# FitFullBoard.net
KiCad netlist of a schematic drawn in EAGLE
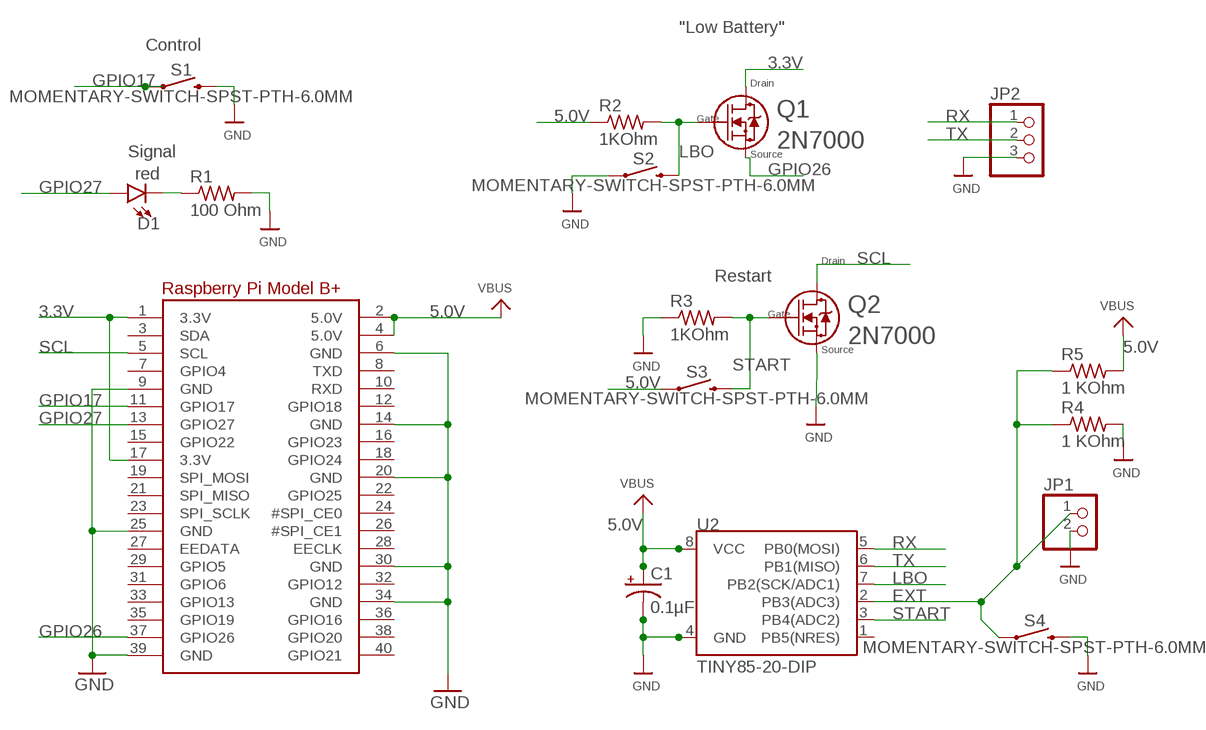
[diagram p0: schematic, sheet 1]

(export (version "E")
  (design (tool "Eeschema 10.0.6"))
  (components
    (comp (ref "C1")
      (value "0.1µF")
      (footprint "eagle-import:E2,5RE")
      (libsource (lib "eagle-import") (part "CPOL-USE2.5-4V"))
    )
    (comp (ref "D1")
      (value "red")
      (footprint "eagle-import:LED_5MM")
      (libsource (lib "eagle-import") (part "LED5MM"))
    )
    (comp (ref "JP1")
      (value "HEADER-1X2")
      (footprint "eagle-import:1X02_OVAL")
      (libsource (lib "eagle-import") (part "HEADER-1X2"))
    )
    (comp (ref "JP2")
      (value "PINHD-1X3CB")
      (footprint "eagle-import:1X03-CLEANBIG")
      (libsource (lib "eagle-import") (part "PINHD-1X3CB"))
    )
    (comp (ref "Q1")
      (value "2N7000")
      (footprint "eagle-import:TO-92")
      (libsource (lib "eagle-import") (part "2N7000"))
    )
    (comp (ref "Q2")
      (value "2N7000")
      (footprint "eagle-import:TO-92")
      (libsource (lib "eagle-import") (part "2N7000"))
    )
    (comp (ref "R1")
      (value "100 Ohm")
      (footprint "eagle-import:0805-THM")
      (libsource (lib "eagle-import") (part "FLIPFLOP-RES"))
    )
    (comp (ref "R2")
      (value "1KOhm")
      (footprint "eagle-import:0805-THM")
      (libsource (lib "eagle-import") (part "FLIPFLOP-RES"))
    )
    (comp (ref "R3")
      (value "1KOhm")
      (footprint "eagle-import:0805-THM")
      (libsource (lib "eagle-import") (part "FLIPFLOP-RES"))
    )
    (comp (ref "R4")
      (value "1 KOhm")
      (footprint "eagle-import:0805-THM")
      (libsource (lib "eagle-import") (part "FLIPFLOP-RES"))
    )
    (comp (ref "R5")
      (value "1 KOhm")
      (footprint "eagle-import:0805-THM")
      (libsource (lib "eagle-import") (part "FLIPFLOP-RES"))
    )
    (comp (ref "RPI1")
      (value "RASPBERRYPI_BPLUS_BONNETNODIM")
      (footprint "eagle-import:PI_BONNET_NODIM")
      (libsource (lib "eagle-import") (part "RASPBERRYPI_BPLUS_BONNETNODIM"))
    )
    (comp (ref "S1")
      (value "MOMENTARY-SWITCH-SPST-PTH-6.0MM")
      (footprint "eagle-import:TACTILE_SWITCH_PTH_6.0MM")
      (libsource (lib "eagle-import") (part "MOMENTARY-SWITCH-SPST-PTH-6.0MM"))
    )
    (comp (ref "S2")
      (value "MOMENTARY-SWITCH-SPST-PTH-6.0MM")
      (footprint "eagle-import:TACTILE_SWITCH_PTH_6.0MM")
      (libsource (lib "eagle-import") (part "MOMENTARY-SWITCH-SPST-PTH-6.0MM"))
    )
    (comp (ref "S3")
      (value "MOMENTARY-SWITCH-SPST-PTH-6.0MM")
      (footprint "eagle-import:TACTILE_SWITCH_PTH_6.0MM")
      (libsource (lib "eagle-import") (part "MOMENTARY-SWITCH-SPST-PTH-6.0MM"))
    )
    (comp (ref "S4")
      (value "MOMENTARY-SWITCH-SPST-PTH-6.0MM")
      (footprint "eagle-import:TACTILE_SWITCH_PTH_6.0MM")
      (libsource (lib "eagle-import") (part "MOMENTARY-SWITCH-SPST-PTH-6.0MM"))
    )
    (comp (ref "U2")
      (value "TINY85-20-DIP")
      (footprint "eagle-import:DIP08_MCU")
      (libsource (lib "eagle-import") (part "ATTINY45TINY85-20-DIP"))
    )
  )
  (nets
    (net (code "1") (name "/3.3V") (class "Default")
      (node (ref "Q1") (pin "3") (pinfunction "2_3") (pintype "passive"))
      (node (ref "RPI1") (pin "1") (pinfunction "3.3V_1") (pintype "power_in"))
      (node (ref "RPI1") (pin "17") (pinfunction "3.3V_17") (pintype "power_in"))
    )
    (net (code "2") (name "/EXT") (class "Default")
      (node (ref "JP1") (pin "1") (pinfunction "1_1") (pintype "passive"))
      (node (ref "R4") (pin "1") (pinfunction "1_1") (pintype "passive"))
      (node (ref "R5") (pin "1") (pinfunction "1_1") (pintype "passive"))
      (node (ref "S4") (pin "1") (pinfunction "1_1") (pintype "passive"))
      (node (ref "U2") (pin "2") (pinfunction "PB3(ADC3)_2") (pintype "bidirectional"))
    )
    (net (code "3") (name "/GPIO17") (class "Default")
      (node (ref "RPI1") (pin "11") (pinfunction "GPIO17_11") (pintype "bidirectional"))
      (node (ref "S1") (pin "1") (pinfunction "1_1") (pintype "passive"))
    )
    (net (code "4") (name "/GPIO26") (class "Default")
      (node (ref "Q1") (pin "1") (pinfunction "3_1") (pintype "passive"))
      (node (ref "RPI1") (pin "37") (pinfunction "GPIO26_37") (pintype "bidirectional"))
    )
    (net (code "5") (name "/GPIO27") (class "Default")
      (node (ref "D1") (pin "A") (pinfunction "A_A") (pintype "passive"))
      (node (ref "RPI1") (pin "13") (pinfunction "GPIO27_13") (pintype "bidirectional"))
    )
    (net (code "6") (name "/LBO") (class "Default")
      (node (ref "Q1") (pin "2") (pinfunction "1_2") (pintype "passive"))
      (node (ref "R2") (pin "2") (pinfunction "2_2") (pintype "passive"))
      (node (ref "S2") (pin "3") (pinfunction "2_3") (pintype "passive"))
      (node (ref "U2") (pin "7") (pinfunction "PB2(SCK/ADC1)_7") (pintype "bidirectional"))
    )
    (net (code "7") (name "/RX") (class "Default")
      (node (ref "JP2") (pin "1") (pinfunction "1_1") (pintype "passive"))
      (node (ref "U2") (pin "5") (pinfunction "PB0(MOSI)_5") (pintype "bidirectional"))
    )
    (net (code "8") (name "/SCL") (class "Default")
      (node (ref "Q2") (pin "3") (pinfunction "2_3") (pintype "passive"))
      (node (ref "RPI1") (pin "5") (pinfunction "SCL_5") (pintype "bidirectional"))
    )
    (net (code "9") (name "/START") (class "Default")
      (node (ref "Q2") (pin "2") (pinfunction "1_2") (pintype "passive"))
      (node (ref "R3") (pin "2") (pinfunction "2_2") (pintype "passive"))
      (node (ref "S3") (pin "3") (pinfunction "2_3") (pintype "passive"))
      (node (ref "U2") (pin "3") (pinfunction "PB4(ADC2)_3") (pintype "bidirectional"))
    )
    (net (code "10") (name "/TX") (class "Default")
      (node (ref "JP2") (pin "2") (pinfunction "2_2") (pintype "passive"))
      (node (ref "U2") (pin "6") (pinfunction "PB1(MISO)_6") (pintype "bidirectional"))
    )
    (net (code "11") (name "GND") (class "Default")
      (node (ref "C1") (pin "-") (pinfunction "-_-") (pintype "passive"))
      (node (ref "JP1") (pin "2") (pinfunction "2_2") (pintype "passive"))
      (node (ref "JP2") (pin "3") (pinfunction "3_3") (pintype "passive"))
      (node (ref "Q2") (pin "1") (pinfunction "3_1") (pintype "passive"))
      (node (ref "R1") (pin "2") (pinfunction "2_2") (pintype "passive"))
      (node (ref "R3") (pin "1") (pinfunction "1_1") (pintype "passive"))
      (node (ref "R4") (pin "2") (pinfunction "2_2") (pintype "passive"))
      (node (ref "RPI1") (pin "14") (pinfunction "GND_14") (pintype "power_in"))
      (node (ref "RPI1") (pin "20") (pinfunction "GND_20") (pintype "power_in"))
      (node (ref "RPI1") (pin "25") (pinfunction "GND_25") (pintype "power_in"))
      (node (ref "RPI1") (pin "30") (pinfunction "GND_30") (pintype "power_in"))
      (node (ref "RPI1") (pin "34") (pinfunction "GND_34") (pintype "power_in"))
      (node (ref "RPI1") (pin "39") (pinfunction "GND_39") (pintype "power_in"))
      (node (ref "RPI1") (pin "6") (pinfunction "GND_6") (pintype "power_in"))
      (node (ref "RPI1") (pin "9") (pinfunction "GND_9") (pintype "power_in"))
      (node (ref "S1") (pin "3") (pinfunction "2_3") (pintype "passive"))
      (node (ref "S2") (pin "1") (pinfunction "1_1") (pintype "passive"))
      (node (ref "S4") (pin "3") (pinfunction "2_3") (pintype "passive"))
      (node (ref "U2") (pin "4") (pinfunction "GND_4") (pintype "bidirectional"))
    )
    (net (code "12") (name "Net-(D1-C)") (class "Default")
      (node (ref "D1") (pin "K") (pinfunction "C_K") (pintype "passive"))
      (node (ref "R1") (pin "1") (pinfunction "1_1") (pintype "passive"))
    )
    (net (code "13") (name "VBUS") (class "Default")
      (node (ref "C1") (pin "+") (pinfunction "+_+") (pintype "passive"))
      (node (ref "R2") (pin "1") (pinfunction "1_1") (pintype "passive"))
      (node (ref "R5") (pin "2") (pinfunction "2_2") (pintype "passive"))
      (node (ref "RPI1") (pin "2") (pinfunction "5.0V_2") (pintype "power_in"))
      (node (ref "RPI1") (pin "4") (pinfunction "5.0V_4") (pintype "power_in"))
      (node (ref "S3") (pin "1") (pinfunction "1_1") (pintype "passive"))
      (node (ref "U2") (pin "8") (pinfunction "VCC_8") (pintype "bidirectional"))
    )
    (net (code "14") (name "unconnected-(RPI1-#SPI_CE0-Pad24)") (class "Default")
      (node (ref "RPI1") (pin "24") (pinfunction "#SPI_CE0_24") (pintype "bidirectional"))
    )
    (net (code "15") (name "unconnected-(RPI1-#SPI_CE1-Pad26)") (class "Default")
      (node (ref "RPI1") (pin "26") (pinfunction "#SPI_CE1_26") (pintype "bidirectional"))
    )
    (net (code "16") (name "unconnected-(RPI1-EECLK-Pad28)") (class "Default")
      (node (ref "RPI1") (pin "28") (pinfunction "EECLK_28") (pintype "bidirectional"))
    )
    (net (code "17") (name "unconnected-(RPI1-EEDATA-Pad27)") (class "Default")
      (node (ref "RPI1") (pin "27") (pinfunction "EEDATA_27") (pintype "bidirectional"))
    )
    (net (code "18") (name "unconnected-(RPI1-GPIO4-Pad7)") (class "Default")
      (node (ref "RPI1") (pin "7") (pinfunction "GPIO4_7") (pintype "bidirectional"))
    )
    (net (code "19") (name "unconnected-(RPI1-GPIO5-Pad29)") (class "Default")
      (node (ref "RPI1") (pin "29") (pinfunction "GPIO5_29") (pintype "bidirectional"))
    )
    (net (code "20") (name "unconnected-(RPI1-GPIO6-Pad31)") (class "Default")
      (node (ref "RPI1") (pin "31") (pinfunction "GPIO6_31") (pintype "bidirectional"))
    )
    (net (code "21") (name "unconnected-(RPI1-GPIO12-Pad32)") (class "Default")
      (node (ref "RPI1") (pin "32") (pinfunction "GPIO12_32") (pintype "bidirectional"))
    )
    (net (code "22") (name "unconnected-(RPI1-GPIO13-Pad33)") (class "Default")
      (node (ref "RPI1") (pin "33") (pinfunction "GPIO13_33") (pintype "bidirectional"))
    )
    (net (code "23") (name "unconnected-(RPI1-GPIO16-Pad36)") (class "Default")
      (node (ref "RPI1") (pin "36") (pinfunction "GPIO16_36") (pintype "bidirectional"))
    )
    (net (code "24") (name "unconnected-(RPI1-GPIO18-Pad12)") (class "Default")
      (node (ref "RPI1") (pin "12") (pinfunction "GPIO18_12") (pintype "bidirectional"))
    )
    (net (code "25") (name "unconnected-(RPI1-GPIO19-Pad35)") (class "Default")
      (node (ref "RPI1") (pin "35") (pinfunction "GPIO19_35") (pintype "bidirectional"))
    )
    (net (code "26") (name "unconnected-(RPI1-GPIO20-Pad38)") (class "Default")
      (node (ref "RPI1") (pin "38") (pinfunction "GPIO20_38") (pintype "bidirectional"))
    )
    (net (code "27") (name "unconnected-(RPI1-GPIO21-Pad40)") (class "Default")
      (node (ref "RPI1") (pin "40") (pinfunction "GPIO21_40") (pintype "bidirectional"))
    )
    (net (code "28") (name "unconnected-(RPI1-GPIO22-Pad15)") (class "Default")
      (node (ref "RPI1") (pin "15") (pinfunction "GPIO22_15") (pintype "bidirectional"))
    )
    (net (code "29") (name "unconnected-(RPI1-GPIO23-Pad16)") (class "Default")
      (node (ref "RPI1") (pin "16") (pinfunction "GPIO23_16") (pintype "bidirectional"))
    )
    (net (code "30") (name "unconnected-(RPI1-GPIO24-Pad18)") (class "Default")
      (node (ref "RPI1") (pin "18") (pinfunction "GPIO24_18") (pintype "bidirectional"))
    )
    (net (code "31") (name "unconnected-(RPI1-GPIO25-Pad22)") (class "Default")
      (node (ref "RPI1") (pin "22") (pinfunction "GPIO25_22") (pintype "bidirectional"))
    )
    (net (code "32") (name "unconnected-(RPI1-RXD-Pad10)") (class "Default")
      (node (ref "RPI1") (pin "10") (pinfunction "RXD_10") (pintype "bidirectional"))
    )
    (net (code "33") (name "unconnected-(RPI1-SDA-Pad3)") (class "Default")
      (node (ref "RPI1") (pin "3") (pinfunction "SDA_3") (pintype "bidirectional"))
    )
    (net (code "34") (name "unconnected-(RPI1-SPI_MISO-Pad21)") (class "Default")
      (node (ref "RPI1") (pin "21") (pinfunction "SPI_MISO_21") (pintype "bidirectional"))
    )
    (net (code "35") (name "unconnected-(RPI1-SPI_MOSI-Pad19)") (class "Default")
      (node (ref "RPI1") (pin "19") (pinfunction "SPI_MOSI_19") (pintype "bidirectional"))
    )
    (net (code "36") (name "unconnected-(RPI1-SPI_SCLK-Pad23)") (class "Default")
      (node (ref "RPI1") (pin "23") (pinfunction "SPI_SCLK_23") (pintype "bidirectional"))
    )
    (net (code "37") (name "unconnected-(RPI1-TXD-Pad8)") (class "Default")
      (node (ref "RPI1") (pin "8") (pinfunction "TXD_8") (pintype "bidirectional"))
    )
    (net (code "38") (name "unconnected-(U2-PB5(NRES)-Pad1)") (class "Default")
      (node (ref "U2") (pin "1") (pinfunction "PB5(NRES)_1") (pintype "bidirectional"))
    )
  )
)
